# 2002_USB.net
KiCad netlist of a schematic drawn in Altium Designer
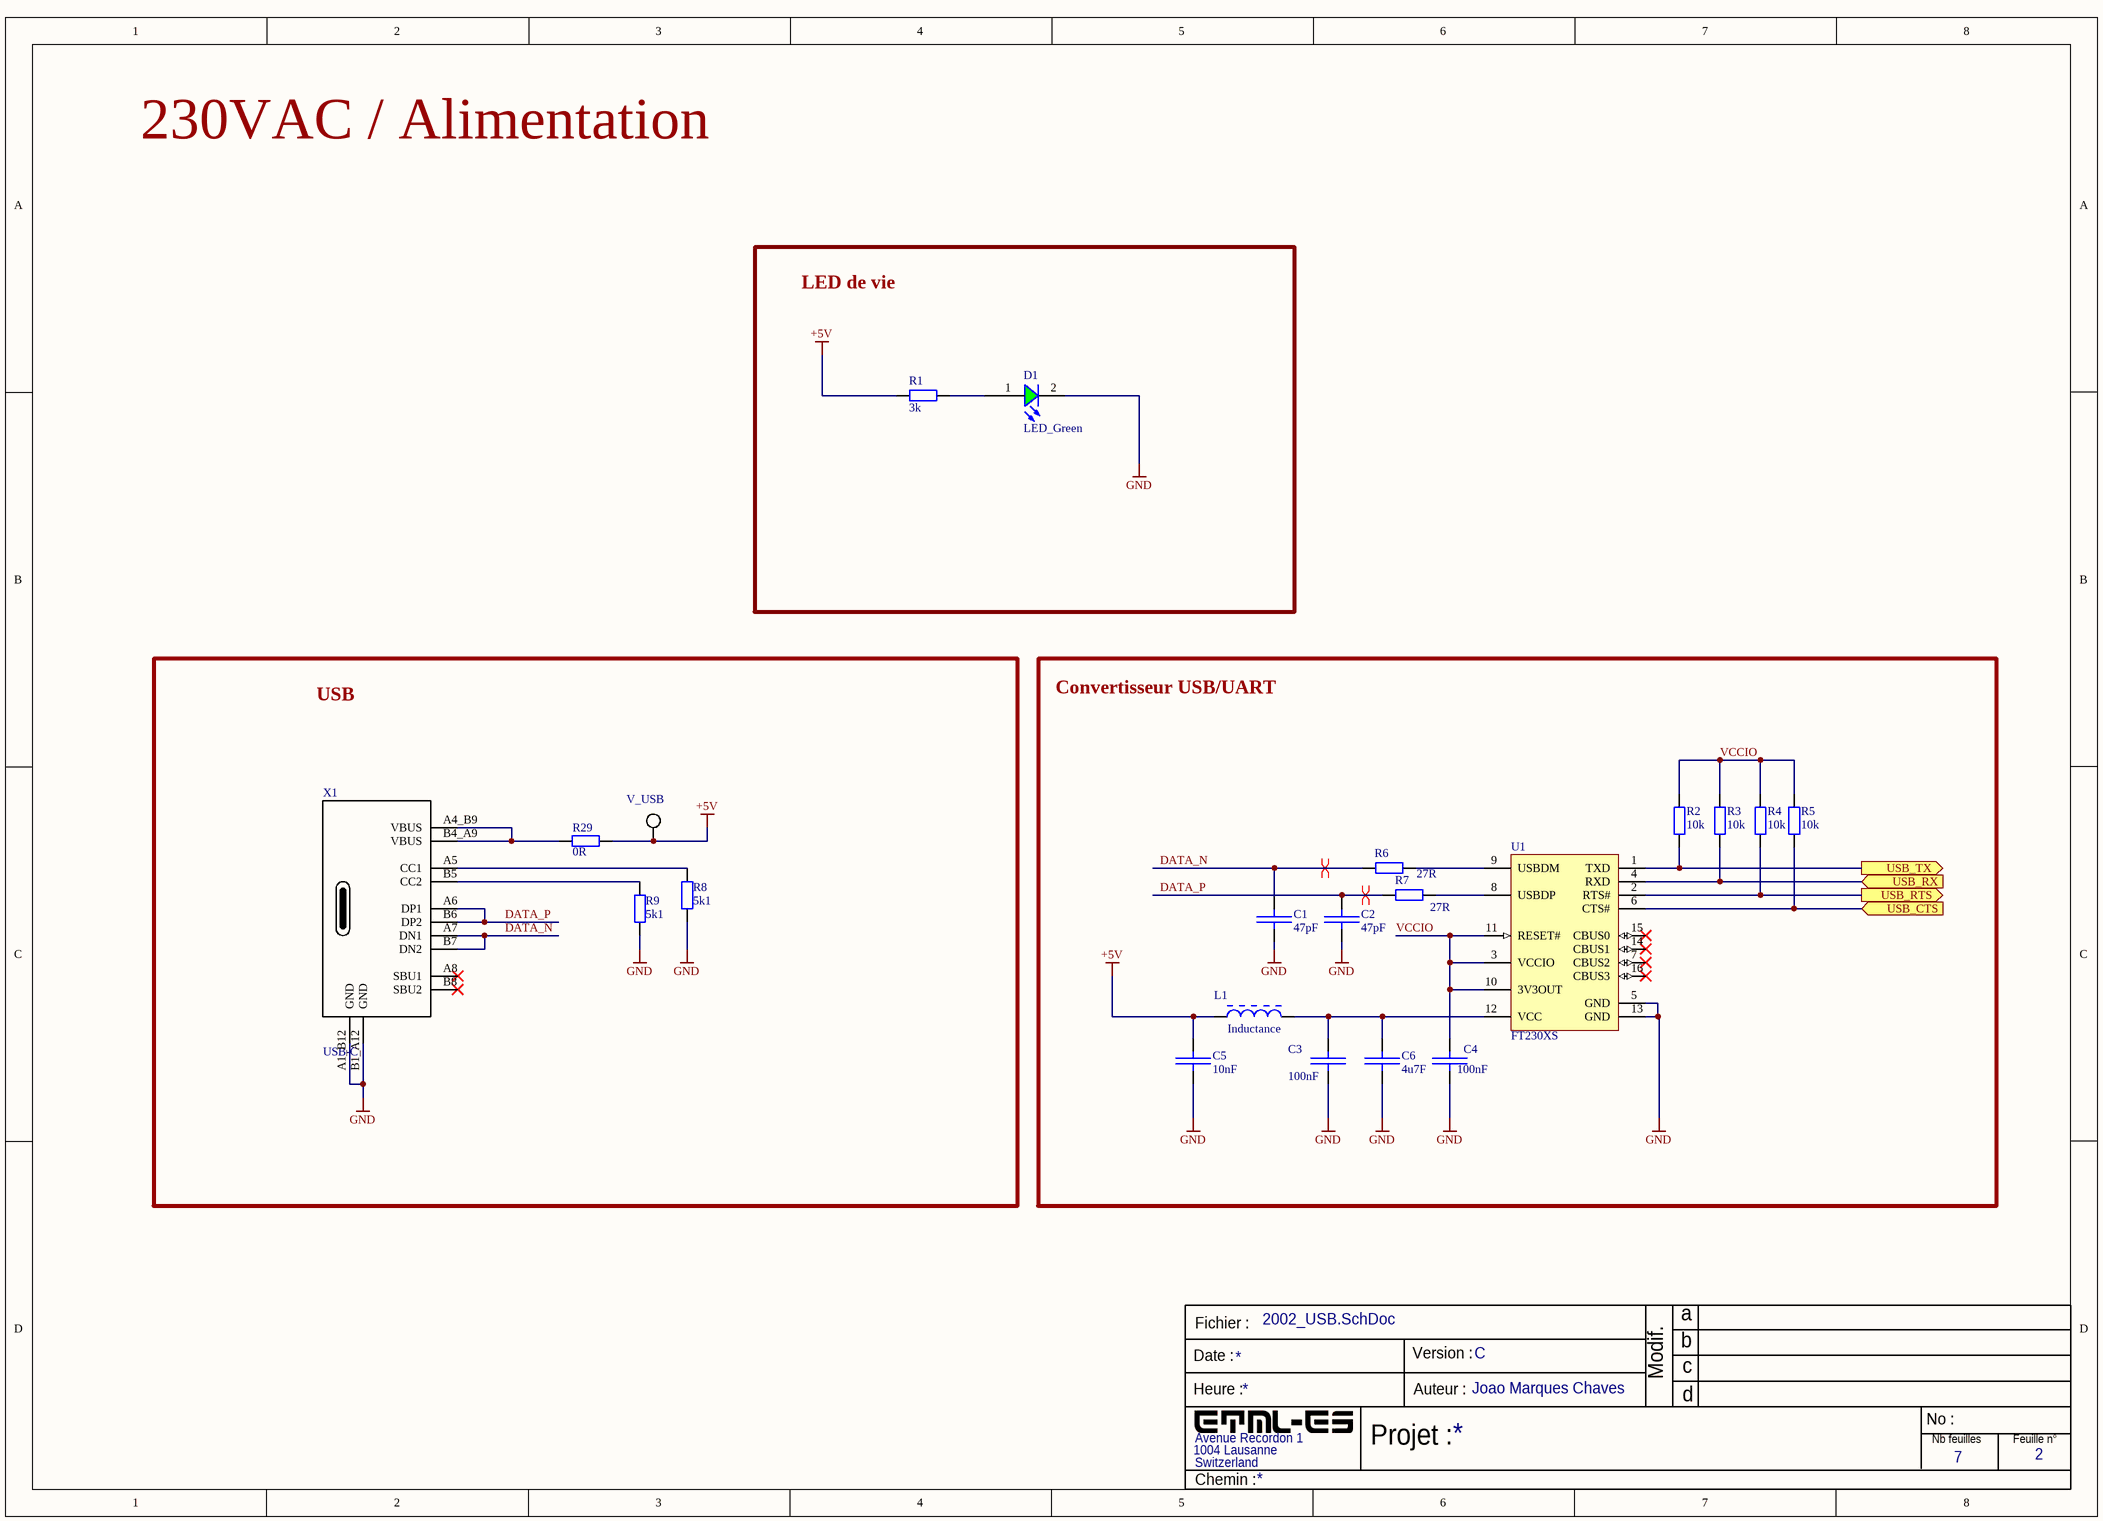
[diagram p0: 2002_USB.SchDoc]

(export (version "E")
  (design (tool "Eeschema 10.0.6"))
  (components
    (comp (ref "C1")
      (value "47pF")
      (footprint "0805")
      (description "Condensator")
      (libsource (lib "2002_CapteurMeteoWifi") (part "Condensator"))
    )
    (comp (ref "C2")
      (value "47pF")
      (footprint "0805")
      (description "Condensator")
      (libsource (lib "2002_CapteurMeteoWifi") (part "Condensator"))
    )
    (comp (ref "C3")
      (value "100nF")
      (footprint "0805")
      (description "0805 Condensator")
      (libsource (lib "2002_CapteurMeteoWifi") (part "Condensator"))
    )
    (comp (ref "C4")
      (value "100nF")
      (footprint "0805")
      (description "0805 Condensator")
      (libsource (lib "2002_CapteurMeteoWifi") (part "Condensator"))
    )
    (comp (ref "C5")
      (value "10nF")
      (footprint "0805")
      (description "0805 Condensator")
      (libsource (lib "2002_CapteurMeteoWifi") (part "Condensator"))
    )
    (comp (ref "C6")
      (value "4u7F")
      (footprint "0805")
      (description "0805 Condensator")
      (libsource (lib "2002_CapteurMeteoWifi") (part "Condensator"))
    )
    (comp (ref "D1")
      (value "LED_Green")
      (footprint "LED_SML-P11VTT86R")
      (libsource (lib "Schlib1") (part "LED_Green"))
    )
    (comp (ref "L1")
      (value "Inductance")
      (footprint "FB_MI0805K601R-10")
      (description "MI0805K601R-10")
      (fields (field (name "MANUFACTURER") "Laird"))
      (libsource (lib "2002_CapteurMeteoWifi") (part "CMP-2000-05196-1"))
    )
    (comp (ref "R1")
      (value "3k")
      (footprint "0805")
      (description "SMD Resistor")
      (fields (field (name "RESISTANCE") "3k"))
      (libsource (lib "2312-MS-0805") (part "RES-0805"))
    )
    (comp (ref "R2")
      (value "10k")
      (footprint "0805")
      (description "SMD Resistor")
      (fields (field (name "RESISTANCE") "10k"))
      (libsource (lib "2312-MS-0805") (part "RES-0805"))
    )
    (comp (ref "R3")
      (value "10k")
      (footprint "0805")
      (description "SMD Resistor")
      (fields (field (name "RESISTANCE") "10k"))
      (libsource (lib "2312-MS-0805") (part "RES-0805"))
    )
    (comp (ref "R4")
      (value "10k")
      (footprint "0805")
      (description "SMD Resistor")
      (fields (field (name "RESISTANCE") "10k"))
      (libsource (lib "2312-MS-0805") (part "RES-0805"))
    )
    (comp (ref "R5")
      (value "10k")
      (footprint "0805")
      (description "SMD Resistor")
      (fields (field (name "RESISTANCE") "10k"))
      (libsource (lib "2312-MS-0805") (part "RES-0805"))
    )
    (comp (ref "R6")
      (value "27R")
      (footprint "0805")
      (description "SMD Resistor 0805, 330Ω")
      (fields (field (name "RESISTANCE") "27R"))
      (libsource (lib "2312-MS-0805") (part "RES-0805"))
    )
    (comp (ref "R7")
      (value "27R")
      (footprint "0805")
      (description "SMD Resistor 0805, 330Ω")
      (fields (field (name "RESISTANCE") "27R"))
      (libsource (lib "2312-MS-0805") (part "RES-0805"))
    )
    (comp (ref "R8")
      (value "5k1")
      (footprint "0805")
      (fields (field (name "PART NUMBER") "ERJ6ENF2703V") (field (name "MANUFACTURER") "Panasonic"))
      (libsource (lib "2121_Robot3roues_V2.0") (part "RES"))
    )
    (comp (ref "R9")
      (value "5k1")
      (footprint "0805")
      (fields (field (name "PART NUMBER") "ERJ6ENF2703V") (field (name "MANUFACTURER") "Panasonic"))
      (libsource (lib "2121_Robot3roues_V2.0") (part "RES"))
    )
    (comp (ref "R29")
      (value "0R")
      (footprint "0805")
      (description "Resistor")
      (fields (field (name "PUBLISHER") "Altium Limited"))
      (libsource (lib "2209_CommandeDomotiqueIR_1") (part "Res2_1"))
    )
    (comp (ref "U1")
      (value "FT230XS")
      (footprint "FTDI-SSOP-16_L")
      (description "USB to Basic UART IC, 2.97 to 5.5 V, -40 to 85 degC, 16-Pin SSOP, RoHS")
      (fields (field (name "MANUFACTURER") "FTDI"))
      (libsource (lib "Schlib1") (part "CMP-2000-06288-1"))
    )
    (comp (ref "V_USB")
      (value "5019")
      (footprint "TESTPOINT_SMD")
      (description "Test point smd")
      (libsource (lib "2002_CapteurMeteoWifi") (part "TESTPOINT"))
    )
    (comp (ref "X1")
      (value "USB-C")
      (footprint "GCT_USB4105-GF-A")
      (description "U262-161N-4BVC11")
      (libsource (lib "Schlib1") (part "USB-C Type 2.0"))
    )
  )
  (nets
    (net (code "1") (name "+5V") (class "Default")
      (node (ref "C5") (pin "1") (pinfunction "1_1") (pintype "passive"))
      (node (ref "L1") (pin "1") (pinfunction "1_1") (pintype "passive"))
      (node (ref "R1") (pin "1") (pinfunction "1_1") (pintype "passive"))
      (node (ref "R29") (pin "2") (pinfunction "2_2") (pintype "passive"))
      (node (ref "V_USB") (pin "1") (pinfunction "1_1") (pintype "passive"))
    )
    (net (code "2") (name "/DATA_N") (class "Default")
      (node (ref "C1") (pin "1") (pinfunction "1_1") (pintype "passive"))
      (node (ref "R6") (pin "1") (pinfunction "1_1") (pintype "passive"))
      (node (ref "X1") (pin "A7") (pinfunction "DN1_A7") (pintype "passive"))
      (node (ref "X1") (pin "B7") (pinfunction "DN2_B7") (pintype "passive"))
    )
    (net (code "3") (name "/DATA_P") (class "Default")
      (node (ref "C2") (pin "1") (pinfunction "1_1") (pintype "passive"))
      (node (ref "R7") (pin "1") (pinfunction "1_1") (pintype "passive"))
      (node (ref "X1") (pin "A6") (pinfunction "DP1_A6") (pintype "passive"))
      (node (ref "X1") (pin "B6") (pinfunction "DP2_B6") (pintype "passive"))
    )
    (net (code "4") (name "/USB_CTS") (class "Default")
      (node (ref "R5") (pin "1") (pinfunction "1_1") (pintype "passive"))
      (node (ref "U1") (pin "6") (pinfunction "CTS#_6") (pintype "passive"))
    )
    (net (code "5") (name "/USB_RTS") (class "Default")
      (node (ref "R4") (pin "1") (pinfunction "1_1") (pintype "passive"))
      (node (ref "U1") (pin "2") (pinfunction "RTS#_2") (pintype "passive"))
    )
    (net (code "6") (name "/USB_RX") (class "Default")
      (node (ref "R3") (pin "1") (pinfunction "1_1") (pintype "passive"))
      (node (ref "U1") (pin "4") (pinfunction "RXD_4") (pintype "passive"))
    )
    (net (code "7") (name "/USB_TX") (class "Default")
      (node (ref "R2") (pin "1") (pinfunction "1_1") (pintype "passive"))
      (node (ref "U1") (pin "1") (pinfunction "TXD_1") (pintype "passive"))
    )
    (net (code "8") (name "/VCCIO") (class "Default")
      (node (ref "C4") (pin "1") (pinfunction "1_1") (pintype "passive"))
      (node (ref "R2") (pin "2") (pinfunction "2_2") (pintype "passive"))
      (node (ref "R3") (pin "2") (pinfunction "2_2") (pintype "passive"))
      (node (ref "R4") (pin "2") (pinfunction "2_2") (pintype "passive"))
      (node (ref "R5") (pin "2") (pinfunction "2_2") (pintype "passive"))
      (node (ref "U1") (pin "10") (pinfunction "3V3OUT_10") (pintype "power_in"))
      (node (ref "U1") (pin "11") (pinfunction "RESET#_11") (pintype "input"))
      (node (ref "U1") (pin "3") (pinfunction "VCCIO_3") (pintype "power_in"))
    )
    (net (code "9") (name "GND") (class "Default")
      (node (ref "C1") (pin "2") (pinfunction "2_2") (pintype "passive"))
      (node (ref "C2") (pin "2") (pinfunction "2_2") (pintype "passive"))
      (node (ref "C3") (pin "2") (pinfunction "2_2") (pintype "passive"))
      (node (ref "C4") (pin "2") (pinfunction "2_2") (pintype "passive"))
      (node (ref "C5") (pin "2") (pinfunction "2_2") (pintype "passive"))
      (node (ref "C6") (pin "2") (pinfunction "2_2") (pintype "passive"))
      (node (ref "D1") (pin "2") (pintype "passive"))
      (node (ref "R8") (pin "1") (pinfunction "1_1") (pintype "passive"))
      (node (ref "R9") (pin "1") (pinfunction "1_1") (pintype "passive"))
      (node (ref "U1") (pin "13") (pinfunction "GND_13") (pintype "power_in"))
      (node (ref "U1") (pin "5") (pinfunction "GND_5") (pintype "power_in"))
      (node (ref "X1") (pin "A1_B12") (pinfunction "GND_A1_B12") (pintype "passive"))
      (node (ref "X1") (pin "B1_A12") (pinfunction "GND_B1_A12") (pintype "passive"))
    )
    (net (code "10") (name "Net-(D1-0)") (class "Default")
      (node (ref "D1") (pin "1") (pinfunction "0_1") (pintype "passive"))
      (node (ref "R1") (pin "2") (pinfunction "2_2") (pintype "passive"))
    )
    (net (code "11") (name "Net-(R29-Pad1)") (class "Default")
      (node (ref "R29") (pin "1") (pinfunction "1_1") (pintype "passive"))
      (node (ref "X1") (pin "A4_B9") (pinfunction "VBUS_A4_B9") (pintype "passive"))
      (node (ref "X1") (pin "B4_A9") (pinfunction "VBUS_B4_A9") (pintype "passive"))
    )
    (net (code "12") (name "Net-(U1-USBDM)") (class "Default")
      (node (ref "R6") (pin "2") (pinfunction "2_2") (pintype "passive"))
      (node (ref "U1") (pin "9") (pinfunction "USBDM_9") (pintype "passive"))
    )
    (net (code "13") (name "Net-(U1-USBDP)") (class "Default")
      (node (ref "R7") (pin "2") (pinfunction "2_2") (pintype "passive"))
      (node (ref "U1") (pin "8") (pinfunction "USBDP_8") (pintype "passive"))
    )
    (net (code "14") (name "Net-(U1-VCC)") (class "Default")
      (node (ref "C3") (pin "1") (pinfunction "1_1") (pintype "passive"))
      (node (ref "C6") (pin "1") (pinfunction "1_1") (pintype "passive"))
      (node (ref "L1") (pin "2") (pinfunction "2_2") (pintype "passive"))
      (node (ref "U1") (pin "12") (pinfunction "VCC_12") (pintype "power_in"))
    )
    (net (code "15") (name "Net-(X1-CC1)") (class "Default")
      (node (ref "R8") (pin "2") (pinfunction "2_2") (pintype "passive"))
      (node (ref "X1") (pin "A5") (pinfunction "CC1_A5") (pintype "passive"))
    )
    (net (code "16") (name "Net-(X1-CC2)") (class "Default")
      (node (ref "R9") (pin "2") (pinfunction "2_2") (pintype "passive"))
      (node (ref "X1") (pin "B5") (pinfunction "CC2_B5") (pintype "passive"))
    )
    (net (code "17") (name "unconnected-(U1-CBUS0-Pad15)") (class "Default")
      (node (ref "U1") (pin "15") (pinfunction "CBUS0_15") (pintype "bidirectional+no_connect"))
    )
    (net (code "18") (name "unconnected-(U1-CBUS1-Pad14)") (class "Default")
      (node (ref "U1") (pin "14") (pinfunction "CBUS1_14") (pintype "bidirectional+no_connect"))
    )
    (net (code "19") (name "unconnected-(U1-CBUS2-Pad7)") (class "Default")
      (node (ref "U1") (pin "7") (pinfunction "CBUS2_7") (pintype "bidirectional+no_connect"))
    )
    (net (code "20") (name "unconnected-(U1-CBUS3-Pad16)") (class "Default")
      (node (ref "U1") (pin "16") (pinfunction "CBUS3_16") (pintype "bidirectional+no_connect"))
    )
    (net (code "21") (name "unconnected-(X1-SBU1-PadA8)") (class "Default")
      (node (ref "X1") (pin "A8") (pinfunction "SBU1_A8") (pintype "passive+no_connect"))
    )
    (net (code "22") (name "unconnected-(X1-SBU2-PadB8)") (class "Default")
      (node (ref "X1") (pin "B8") (pinfunction "SBU2_B8") (pintype "passive+no_connect"))
    )
  )
)
